# circuit1.net
KiCad netlist of a schematic drawn in EAGLE
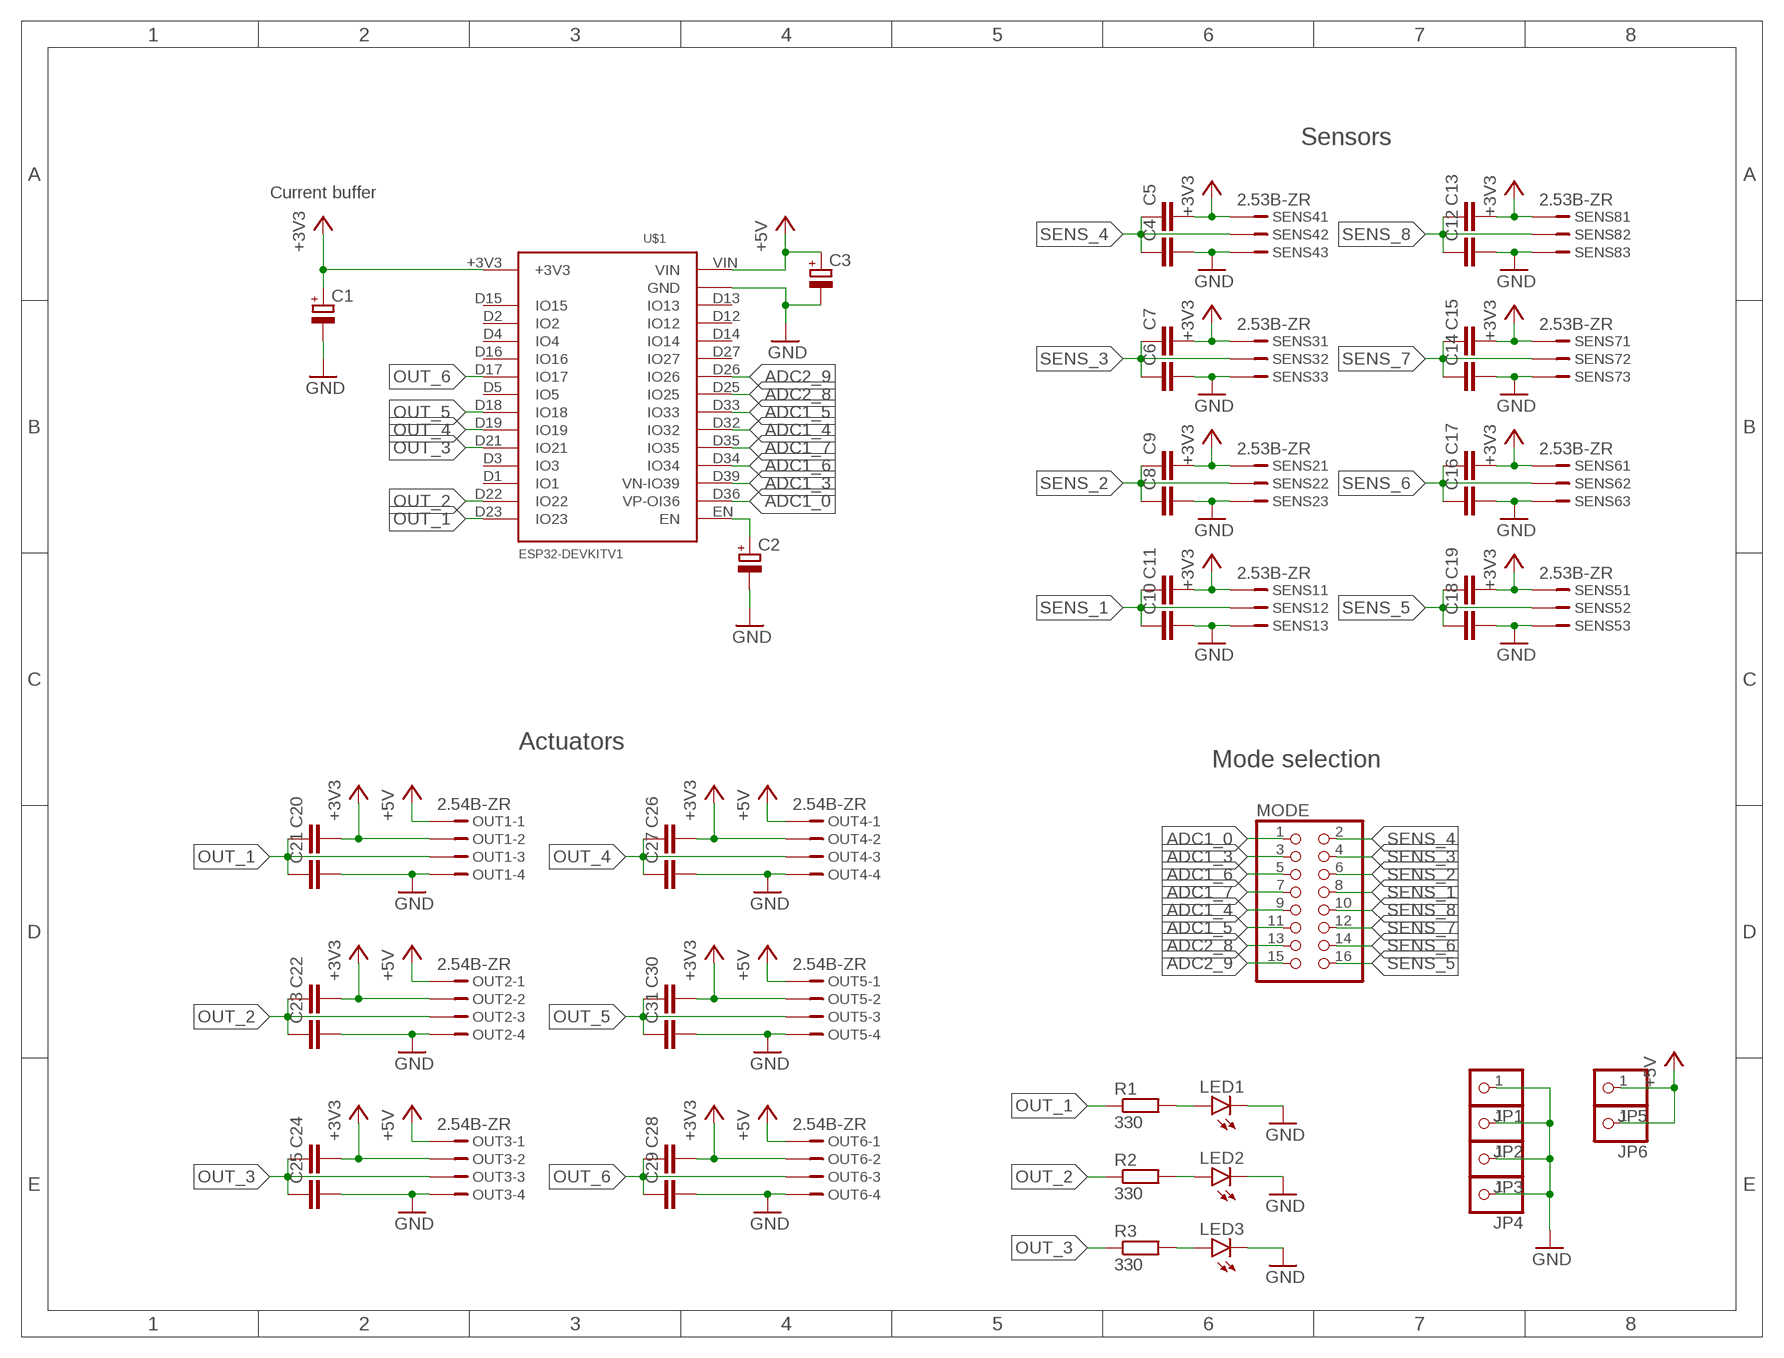
[diagram p0: schematic, sheet 1]

(export (version "E")
  (design (tool "Eeschema 10.0.6"))
  (components
    (comp (ref "C1")
      (value "CPOL-EUE3.5-8")
      (footprint "eagle-import:E3,5-8")
      (libsource (lib "eagle-import") (part "CPOL-EUE3.5-8"))
    )
    (comp (ref "C2")
      (value "CPOL-EUE3.5-8")
      (footprint "eagle-import:E3,5-8")
      (libsource (lib "eagle-import") (part "CPOL-EUE3.5-8"))
    )
    (comp (ref "C3")
      (value "CPOL-EUE3.5-8")
      (footprint "eagle-import:E3,5-8")
      (libsource (lib "eagle-import") (part "CPOL-EUE3.5-8"))
    )
    (comp (ref "C4")
      (value "C-EU025-030X050")
      (footprint "eagle-import:C025-030X050")
      (libsource (lib "eagle-import") (part "C-EU025-030X050"))
    )
    (comp (ref "C5")
      (value "C-EU025-030X050")
      (footprint "eagle-import:C025-030X050")
      (libsource (lib "eagle-import") (part "C-EU025-030X050"))
    )
    (comp (ref "C6")
      (value "C-EU025-030X050")
      (footprint "eagle-import:C025-030X050")
      (libsource (lib "eagle-import") (part "C-EU025-030X050"))
    )
    (comp (ref "C7")
      (value "C-EU025-030X050")
      (footprint "eagle-import:C025-030X050")
      (libsource (lib "eagle-import") (part "C-EU025-030X050"))
    )
    (comp (ref "C8")
      (value "C-EU025-030X050")
      (footprint "eagle-import:C025-030X050")
      (libsource (lib "eagle-import") (part "C-EU025-030X050"))
    )
    (comp (ref "C9")
      (value "C-EU025-030X050")
      (footprint "eagle-import:C025-030X050")
      (libsource (lib "eagle-import") (part "C-EU025-030X050"))
    )
    (comp (ref "C10")
      (value "C-EU025-030X050")
      (footprint "eagle-import:C025-030X050")
      (libsource (lib "eagle-import") (part "C-EU025-030X050"))
    )
    (comp (ref "C11")
      (value "C-EU025-030X050")
      (footprint "eagle-import:C025-030X050")
      (libsource (lib "eagle-import") (part "C-EU025-030X050"))
    )
    (comp (ref "C12")
      (value "C-EU025-030X050")
      (footprint "eagle-import:C025-030X050")
      (libsource (lib "eagle-import") (part "C-EU025-030X050"))
    )
    (comp (ref "C13")
      (value "C-EU025-030X050")
      (footprint "eagle-import:C025-030X050")
      (libsource (lib "eagle-import") (part "C-EU025-030X050"))
    )
    (comp (ref "C14")
      (value "C-EU025-030X050")
      (footprint "eagle-import:C025-030X050")
      (libsource (lib "eagle-import") (part "C-EU025-030X050"))
    )
    (comp (ref "C15")
      (value "C-EU025-030X050")
      (footprint "eagle-import:C025-030X050")
      (libsource (lib "eagle-import") (part "C-EU025-030X050"))
    )
    (comp (ref "C16")
      (value "C-EU025-030X050")
      (footprint "eagle-import:C025-030X050")
      (libsource (lib "eagle-import") (part "C-EU025-030X050"))
    )
    (comp (ref "C17")
      (value "C-EU025-030X050")
      (footprint "eagle-import:C025-030X050")
      (libsource (lib "eagle-import") (part "C-EU025-030X050"))
    )
    (comp (ref "C18")
      (value "C-EU025-030X050")
      (footprint "eagle-import:C025-030X050")
      (libsource (lib "eagle-import") (part "C-EU025-030X050"))
    )
    (comp (ref "C19")
      (value "C-EU025-030X050")
      (footprint "eagle-import:C025-030X050")
      (libsource (lib "eagle-import") (part "C-EU025-030X050"))
    )
    (comp (ref "C20")
      (value "C-EU025-030X050")
      (footprint "eagle-import:C025-030X050")
      (libsource (lib "eagle-import") (part "C-EU025-030X050"))
    )
    (comp (ref "C21")
      (value "C-EU025-030X050")
      (footprint "eagle-import:C025-030X050")
      (libsource (lib "eagle-import") (part "C-EU025-030X050"))
    )
    (comp (ref "C22")
      (value "C-EU025-030X050")
      (footprint "eagle-import:C025-030X050")
      (libsource (lib "eagle-import") (part "C-EU025-030X050"))
    )
    (comp (ref "C23")
      (value "C-EU025-030X050")
      (footprint "eagle-import:C025-030X050")
      (libsource (lib "eagle-import") (part "C-EU025-030X050"))
    )
    (comp (ref "C24")
      (value "C-EU025-030X050")
      (footprint "eagle-import:C025-030X050")
      (libsource (lib "eagle-import") (part "C-EU025-030X050"))
    )
    (comp (ref "C25")
      (value "C-EU025-030X050")
      (footprint "eagle-import:C025-030X050")
      (libsource (lib "eagle-import") (part "C-EU025-030X050"))
    )
    (comp (ref "C26")
      (value "C-EU025-030X050")
      (footprint "eagle-import:C025-030X050")
      (libsource (lib "eagle-import") (part "C-EU025-030X050"))
    )
    (comp (ref "C27")
      (value "C-EU025-030X050")
      (footprint "eagle-import:C025-030X050")
      (libsource (lib "eagle-import") (part "C-EU025-030X050"))
    )
    (comp (ref "C28")
      (value "C-EU025-030X050")
      (footprint "eagle-import:C025-030X050")
      (libsource (lib "eagle-import") (part "C-EU025-030X050"))
    )
    (comp (ref "C29")
      (value "C-EU025-030X050")
      (footprint "eagle-import:C025-030X050")
      (libsource (lib "eagle-import") (part "C-EU025-030X050"))
    )
    (comp (ref "C30")
      (value "C-EU025-030X050")
      (footprint "eagle-import:C025-030X050")
      (libsource (lib "eagle-import") (part "C-EU025-030X050"))
    )
    (comp (ref "C31")
      (value "C-EU025-030X050")
      (footprint "eagle-import:C025-030X050")
      (libsource (lib "eagle-import") (part "C-EU025-030X050"))
    )
    (comp (ref "JP1")
      (value "PINHD-1X1")
      (footprint "eagle-import:1X01")
      (libsource (lib "eagle-import") (part "PINHD-1X1"))
    )
    (comp (ref "JP2")
      (value "PINHD-1X1")
      (footprint "eagle-import:1X01")
      (libsource (lib "eagle-import") (part "PINHD-1X1"))
    )
    (comp (ref "JP3")
      (value "PINHD-1X1")
      (footprint "eagle-import:1X01")
      (libsource (lib "eagle-import") (part "PINHD-1X1"))
    )
    (comp (ref "JP4")
      (value "PINHD-1X1")
      (footprint "eagle-import:1X01")
      (libsource (lib "eagle-import") (part "PINHD-1X1"))
    )
    (comp (ref "JP5")
      (value "PINHD-1X1")
      (footprint "eagle-import:1X01")
      (libsource (lib "eagle-import") (part "PINHD-1X1"))
    )
    (comp (ref "JP6")
      (value "PINHD-1X1")
      (footprint "eagle-import:1X01")
      (libsource (lib "eagle-import") (part "PINHD-1X1"))
    )
    (comp (ref "LED1")
      (value "LED3MM")
      (footprint "eagle-import:LED3MM")
      (libsource (lib "eagle-import") (part "LED3MM"))
    )
    (comp (ref "LED2")
      (value "LED3MM")
      (footprint "eagle-import:LED3MM")
      (libsource (lib "eagle-import") (part "LED3MM"))
    )
    (comp (ref "LED3")
      (value "LED3MM")
      (footprint "eagle-import:LED3MM")
      (libsource (lib "eagle-import") (part "LED3MM"))
    )
    (comp (ref "MODE")
      (value "PINHD-2X8")
      (footprint "eagle-import:2X08")
      (libsource (lib "eagle-import") (part "PINHD-2X8"))
    )
    (comp (ref "OUT1")
      (value "2.54B-ZR")
      (footprint "eagle-import:B4B-ZR2.5")
      (libsource (lib "eagle-import") (part "?4B-ZR2.5"))
    )
    (comp (ref "OUT2")
      (value "2.54B-ZR")
      (footprint "eagle-import:B4B-ZR2.5")
      (libsource (lib "eagle-import") (part "?4B-ZR2.5"))
    )
    (comp (ref "OUT3")
      (value "2.54B-ZR")
      (footprint "eagle-import:B4B-ZR2.5")
      (libsource (lib "eagle-import") (part "?4B-ZR2.5"))
    )
    (comp (ref "OUT4")
      (value "2.54B-ZR")
      (footprint "eagle-import:B4B-ZR2.5")
      (libsource (lib "eagle-import") (part "?4B-ZR2.5"))
    )
    (comp (ref "OUT5")
      (value "2.54B-ZR")
      (footprint "eagle-import:B4B-ZR2.5")
      (libsource (lib "eagle-import") (part "?4B-ZR2.5"))
    )
    (comp (ref "OUT6")
      (value "2.54B-ZR")
      (footprint "eagle-import:B4B-ZR2.5")
      (libsource (lib "eagle-import") (part "?4B-ZR2.5"))
    )
    (comp (ref "R1")
      (value "330")
      (footprint "eagle-import:0204_7")
      (libsource (lib "eagle-import") (part "R-EU_0204/7"))
    )
    (comp (ref "R2")
      (value "330")
      (footprint "eagle-import:0204_7")
      (libsource (lib "eagle-import") (part "R-EU_0204/7"))
    )
    (comp (ref "R3")
      (value "330")
      (footprint "eagle-import:0204_7")
      (libsource (lib "eagle-import") (part "R-EU_0204/7"))
    )
    (comp (ref "SENS1")
      (value "2.53B-ZR")
      (footprint "eagle-import:B3B-ZR2.5")
      (libsource (lib "eagle-import") (part "?3B-ZR2.5"))
    )
    (comp (ref "SENS2")
      (value "2.53B-ZR")
      (footprint "eagle-import:B3B-ZR2.5")
      (libsource (lib "eagle-import") (part "?3B-ZR2.5"))
    )
    (comp (ref "SENS3")
      (value "2.53B-ZR")
      (footprint "eagle-import:B3B-ZR2.5")
      (libsource (lib "eagle-import") (part "?3B-ZR2.5"))
    )
    (comp (ref "SENS4")
      (value "2.53B-ZR")
      (footprint "eagle-import:B3B-ZR2.5")
      (libsource (lib "eagle-import") (part "?3B-ZR2.5"))
    )
    (comp (ref "SENS5")
      (value "2.53B-ZR")
      (footprint "eagle-import:B3B-ZR2.5")
      (libsource (lib "eagle-import") (part "?3B-ZR2.5"))
    )
    (comp (ref "SENS6")
      (value "2.53B-ZR")
      (footprint "eagle-import:B3B-ZR2.5")
      (libsource (lib "eagle-import") (part "?3B-ZR2.5"))
    )
    (comp (ref "SENS7")
      (value "2.53B-ZR")
      (footprint "eagle-import:B3B-ZR2.5")
      (libsource (lib "eagle-import") (part "?3B-ZR2.5"))
    )
    (comp (ref "SENS8")
      (value "2.53B-ZR")
      (footprint "eagle-import:B3B-ZR2.5")
      (libsource (lib "eagle-import") (part "?3B-ZR2.5"))
    )
    (comp (ref "U$1")
      (value "ESP32DEVKITV1")
      (footprint "eagle-import:ESP32-DEVKITV1")
      (libsource (lib "eagle-import") (part "ESP32DEVKITV1"))
    )
  )
  (nets
    (net (code "1") (name "+3V3") (class "Default")
      (node (ref "C1") (pin "+") (pinfunction "+_+") (pintype "passive"))
      (node (ref "C11") (pin "2") (pinfunction "2_2") (pintype "passive"))
      (node (ref "C13") (pin "2") (pinfunction "2_2") (pintype "passive"))
      (node (ref "C15") (pin "2") (pinfunction "2_2") (pintype "passive"))
      (node (ref "C17") (pin "2") (pinfunction "2_2") (pintype "passive"))
      (node (ref "C19") (pin "2") (pinfunction "2_2") (pintype "passive"))
      (node (ref "C20") (pin "2") (pinfunction "2_2") (pintype "passive"))
      (node (ref "C22") (pin "2") (pinfunction "2_2") (pintype "passive"))
      (node (ref "C24") (pin "2") (pinfunction "2_2") (pintype "passive"))
      (node (ref "C26") (pin "2") (pinfunction "2_2") (pintype "passive"))
      (node (ref "C28") (pin "2") (pinfunction "2_2") (pintype "passive"))
      (node (ref "C30") (pin "2") (pinfunction "2_2") (pintype "passive"))
      (node (ref "C5") (pin "2") (pinfunction "2_2") (pintype "passive"))
      (node (ref "C7") (pin "2") (pinfunction "2_2") (pintype "passive"))
      (node (ref "C9") (pin "2") (pinfunction "2_2") (pintype "passive"))
      (node (ref "OUT1") (pin "2") (pinfunction "1_2") (pintype "passive"))
      (node (ref "OUT2") (pin "2") (pinfunction "1_2") (pintype "passive"))
      (node (ref "OUT3") (pin "2") (pinfunction "1_2") (pintype "passive"))
      (node (ref "OUT4") (pin "2") (pinfunction "1_2") (pintype "passive"))
      (node (ref "OUT5") (pin "2") (pinfunction "1_2") (pintype "passive"))
      (node (ref "OUT6") (pin "2") (pinfunction "1_2") (pintype "passive"))
      (node (ref "SENS1") (pin "1") (pinfunction "1_1") (pintype "passive"))
      (node (ref "SENS2") (pin "1") (pinfunction "1_1") (pintype "passive"))
      (node (ref "SENS3") (pin "1") (pinfunction "1_1") (pintype "passive"))
      (node (ref "SENS4") (pin "1") (pinfunction "1_1") (pintype "passive"))
      (node (ref "SENS5") (pin "1") (pinfunction "1_1") (pintype "passive"))
      (node (ref "SENS6") (pin "1") (pinfunction "1_1") (pintype "passive"))
      (node (ref "SENS7") (pin "1") (pinfunction "1_1") (pintype "passive"))
      (node (ref "SENS8") (pin "1") (pinfunction "1_1") (pintype "passive"))
      (node (ref "U$1") (pin "+3V3") (pinfunction "+3V3_+3V3") (pintype "power_in"))
    )
    (net (code "2") (name "+5V") (class "Default")
      (node (ref "C3") (pin "+") (pinfunction "+_+") (pintype "passive"))
      (node (ref "JP5") (pin "1") (pinfunction "1_1") (pintype "passive"))
      (node (ref "JP6") (pin "1") (pinfunction "1_1") (pintype "passive"))
      (node (ref "OUT1") (pin "1") (pinfunction "1_1") (pintype "passive"))
      (node (ref "OUT2") (pin "1") (pinfunction "1_1") (pintype "passive"))
      (node (ref "OUT3") (pin "1") (pinfunction "1_1") (pintype "passive"))
      (node (ref "OUT4") (pin "1") (pinfunction "1_1") (pintype "passive"))
      (node (ref "OUT5") (pin "1") (pinfunction "1_1") (pintype "passive"))
      (node (ref "OUT6") (pin "1") (pinfunction "1_1") (pintype "passive"))
      (node (ref "U$1") (pin "VIN") (pinfunction "VIN_VIN") (pintype "power_in"))
    )
    (net (code "3") (name "ADC1_0") (class "Default")
      (node (ref "MODE") (pin "1") (pinfunction "1_1") (pintype "passive"))
      (node (ref "U$1") (pin "D36") (pinfunction "VP-OI36_D36") (pintype "bidirectional"))
    )
    (net (code "4") (name "ADC1_3") (class "Default")
      (node (ref "MODE") (pin "3") (pinfunction "3_3") (pintype "passive"))
      (node (ref "U$1") (pin "D39") (pinfunction "VN-IO39_D39") (pintype "bidirectional"))
    )
    (net (code "5") (name "ADC1_4") (class "Default")
      (node (ref "MODE") (pin "9") (pinfunction "9_9") (pintype "passive"))
      (node (ref "U$1") (pin "D32") (pinfunction "IO32_D32") (pintype "bidirectional"))
    )
    (net (code "6") (name "ADC1_5") (class "Default")
      (node (ref "MODE") (pin "11") (pinfunction "11_11") (pintype "passive"))
      (node (ref "U$1") (pin "D33") (pinfunction "IO33_D33") (pintype "bidirectional"))
    )
    (net (code "7") (name "ADC1_6") (class "Default")
      (node (ref "MODE") (pin "5") (pinfunction "5_5") (pintype "passive"))
      (node (ref "U$1") (pin "D34") (pinfunction "IO34_D34") (pintype "bidirectional"))
    )
    (net (code "8") (name "ADC1_7") (class "Default")
      (node (ref "MODE") (pin "7") (pinfunction "7_7") (pintype "passive"))
      (node (ref "U$1") (pin "D35") (pinfunction "IO35_D35") (pintype "bidirectional"))
    )
    (net (code "9") (name "ADC2_8") (class "Default")
      (node (ref "MODE") (pin "13") (pinfunction "13_13") (pintype "passive"))
      (node (ref "U$1") (pin "D25") (pinfunction "IO25_D25") (pintype "bidirectional"))
    )
    (net (code "10") (name "ADC2_9") (class "Default")
      (node (ref "MODE") (pin "15") (pinfunction "15_15") (pintype "passive"))
      (node (ref "U$1") (pin "D26") (pinfunction "IO26_D26") (pintype "bidirectional"))
    )
    (net (code "11") (name "GND") (class "Default")
      (node (ref "C1") (pin "-") (pinfunction "-_-") (pintype "passive"))
      (node (ref "C10") (pin "2") (pinfunction "2_2") (pintype "passive"))
      (node (ref "C12") (pin "2") (pinfunction "2_2") (pintype "passive"))
      (node (ref "C14") (pin "2") (pinfunction "2_2") (pintype "passive"))
      (node (ref "C16") (pin "2") (pinfunction "2_2") (pintype "passive"))
      (node (ref "C18") (pin "2") (pinfunction "2_2") (pintype "passive"))
      (node (ref "C2") (pin "-") (pinfunction "-_-") (pintype "passive"))
      (node (ref "C21") (pin "2") (pinfunction "2_2") (pintype "passive"))
      (node (ref "C23") (pin "2") (pinfunction "2_2") (pintype "passive"))
      (node (ref "C25") (pin "2") (pinfunction "2_2") (pintype "passive"))
      (node (ref "C27") (pin "2") (pinfunction "2_2") (pintype "passive"))
      (node (ref "C29") (pin "2") (pinfunction "2_2") (pintype "passive"))
      (node (ref "C3") (pin "-") (pinfunction "-_-") (pintype "passive"))
      (node (ref "C31") (pin "2") (pinfunction "2_2") (pintype "passive"))
      (node (ref "C4") (pin "2") (pinfunction "2_2") (pintype "passive"))
      (node (ref "C6") (pin "2") (pinfunction "2_2") (pintype "passive"))
      (node (ref "C8") (pin "2") (pinfunction "2_2") (pintype "passive"))
      (node (ref "JP1") (pin "1") (pinfunction "1_1") (pintype "passive"))
      (node (ref "JP2") (pin "1") (pinfunction "1_1") (pintype "passive"))
      (node (ref "JP3") (pin "1") (pinfunction "1_1") (pintype "passive"))
      (node (ref "JP4") (pin "1") (pinfunction "1_1") (pintype "passive"))
      (node (ref "LED1") (pin "K") (pinfunction "C_K") (pintype "passive"))
      (node (ref "LED2") (pin "K") (pinfunction "C_K") (pintype "passive"))
      (node (ref "LED3") (pin "K") (pinfunction "C_K") (pintype "passive"))
      (node (ref "OUT1") (pin "4") (pinfunction "1_4") (pintype "passive"))
      (node (ref "OUT2") (pin "4") (pinfunction "1_4") (pintype "passive"))
      (node (ref "OUT3") (pin "4") (pinfunction "1_4") (pintype "passive"))
      (node (ref "OUT4") (pin "4") (pinfunction "1_4") (pintype "passive"))
      (node (ref "OUT5") (pin "4") (pinfunction "1_4") (pintype "passive"))
      (node (ref "OUT6") (pin "4") (pinfunction "1_4") (pintype "passive"))
      (node (ref "SENS1") (pin "3") (pinfunction "1_3") (pintype "passive"))
      (node (ref "SENS2") (pin "3") (pinfunction "1_3") (pintype "passive"))
      (node (ref "SENS3") (pin "3") (pinfunction "1_3") (pintype "passive"))
      (node (ref "SENS4") (pin "3") (pinfunction "1_3") (pintype "passive"))
      (node (ref "SENS5") (pin "3") (pinfunction "1_3") (pintype "passive"))
      (node (ref "SENS6") (pin "3") (pinfunction "1_3") (pintype "passive"))
      (node (ref "SENS7") (pin "3") (pinfunction "1_3") (pintype "passive"))
      (node (ref "SENS8") (pin "3") (pinfunction "1_3") (pintype "passive"))
      (node (ref "U$1") (pin "GND") (pinfunction "GND_GND") (pintype "output"))
      (node (ref "U$1") (pin "GND@2") (pinfunction "GND_GND@2") (pintype "output"))
    )
    (net (code "12") (name "Net-(C2-Pad+)") (class "Default")
      (node (ref "C2") (pin "+") (pinfunction "+_+") (pintype "passive"))
      (node (ref "U$1") (pin "EN") (pinfunction "EN_EN") (pintype "bidirectional"))
    )
    (net (code "13") (name "Net-(LED1-PadA)") (class "Default")
      (node (ref "LED1") (pin "A") (pinfunction "A_A") (pintype "passive"))
      (node (ref "R1") (pin "2") (pinfunction "2_2") (pintype "passive"))
    )
    (net (code "14") (name "Net-(LED2-PadA)") (class "Default")
      (node (ref "LED2") (pin "A") (pinfunction "A_A") (pintype "passive"))
      (node (ref "R2") (pin "2") (pinfunction "2_2") (pintype "passive"))
    )
    (net (code "15") (name "Net-(LED3-PadA)") (class "Default")
      (node (ref "LED3") (pin "A") (pinfunction "A_A") (pintype "passive"))
      (node (ref "R3") (pin "2") (pinfunction "2_2") (pintype "passive"))
    )
    (net (code "16") (name "OUT_1") (class "Default")
      (node (ref "C20") (pin "1") (pinfunction "1_1") (pintype "passive"))
      (node (ref "C21") (pin "1") (pinfunction "1_1") (pintype "passive"))
      (node (ref "OUT1") (pin "3") (pinfunction "1_3") (pintype "passive"))
      (node (ref "R1") (pin "1") (pinfunction "1_1") (pintype "passive"))
      (node (ref "U$1") (pin "D23") (pinfunction "IO23_D23") (pintype "bidirectional"))
    )
    (net (code "17") (name "OUT_2") (class "Default")
      (node (ref "C22") (pin "1") (pinfunction "1_1") (pintype "passive"))
      (node (ref "C23") (pin "1") (pinfunction "1_1") (pintype "passive"))
      (node (ref "OUT2") (pin "3") (pinfunction "1_3") (pintype "passive"))
      (node (ref "R2") (pin "1") (pinfunction "1_1") (pintype "passive"))
      (node (ref "U$1") (pin "D22") (pinfunction "IO22_D22") (pintype "bidirectional"))
    )
    (net (code "18") (name "OUT_3") (class "Default")
      (node (ref "C24") (pin "1") (pinfunction "1_1") (pintype "passive"))
      (node (ref "C25") (pin "1") (pinfunction "1_1") (pintype "passive"))
      (node (ref "OUT3") (pin "3") (pinfunction "1_3") (pintype "passive"))
      (node (ref "R3") (pin "1") (pinfunction "1_1") (pintype "passive"))
      (node (ref "U$1") (pin "D21") (pinfunction "IO21_D21") (pintype "bidirectional"))
    )
    (net (code "19") (name "OUT_4") (class "Default")
      (node (ref "C26") (pin "1") (pinfunction "1_1") (pintype "passive"))
      (node (ref "C27") (pin "1") (pinfunction "1_1") (pintype "passive"))
      (node (ref "OUT4") (pin "3") (pinfunction "1_3") (pintype "passive"))
      (node (ref "U$1") (pin "D19") (pinfunction "IO19_D19") (pintype "bidirectional"))
    )
    (net (code "20") (name "OUT_5") (class "Default")
      (node (ref "C30") (pin "1") (pinfunction "1_1") (pintype "passive"))
      (node (ref "C31") (pin "1") (pinfunction "1_1") (pintype "passive"))
      (node (ref "OUT5") (pin "3") (pinfunction "1_3") (pintype "passive"))
      (node (ref "U$1") (pin "D18") (pinfunction "IO18_D18") (pintype "bidirectional"))
    )
    (net (code "21") (name "OUT_6") (class "Default")
      (node (ref "C28") (pin "1") (pinfunction "1_1") (pintype "passive"))
      (node (ref "C29") (pin "1") (pinfunction "1_1") (pintype "passive"))
      (node (ref "OUT6") (pin "3") (pinfunction "1_3") (pintype "passive"))
      (node (ref "U$1") (pin "D17") (pinfunction "IO17_D17") (pintype "bidirectional"))
    )
    (net (code "22") (name "SENS_1") (class "Default")
      (node (ref "C10") (pin "1") (pinfunction "1_1") (pintype "passive"))
      (node (ref "C11") (pin "1") (pinfunction "1_1") (pintype "passive"))
      (node (ref "MODE") (pin "8") (pinfunction "8_8") (pintype "passive"))
      (node (ref "SENS1") (pin "2") (pinfunction "1_2") (pintype "passive"))
    )
    (net (code "23") (name "SENS_2") (class "Default")
      (node (ref "C8") (pin "1") (pinfunction "1_1") (pintype "passive"))
      (node (ref "C9") (pin "1") (pinfunction "1_1") (pintype "passive"))
      (node (ref "MODE") (pin "6") (pinfunction "6_6") (pintype "passive"))
      (node (ref "SENS2") (pin "2") (pinfunction "1_2") (pintype "passive"))
    )
    (net (code "24") (name "SENS_3") (class "Default")
      (node (ref "C6") (pin "1") (pinfunction "1_1") (pintype "passive"))
      (node (ref "C7") (pin "1") (pinfunction "1_1") (pintype "passive"))
      (node (ref "MODE") (pin "4") (pinfunction "4_4") (pintype "passive"))
      (node (ref "SENS3") (pin "2") (pinfunction "1_2") (pintype "passive"))
    )
    (net (code "25") (name "SENS_4") (class "Default")
      (node (ref "C4") (pin "1") (pinfunction "1_1") (pintype "passive"))
      (node (ref "C5") (pin "1") (pinfunction "1_1") (pintype "passive"))
      (node (ref "MODE") (pin "2") (pinfunction "2_2") (pintype "passive"))
      (node (ref "SENS4") (pin "2") (pinfunction "1_2") (pintype "passive"))
    )
    (net (code "26") (name "SENS_5") (class "Default")
      (node (ref "C18") (pin "1") (pinfunction "1_1") (pintype "passive"))
      (node (ref "C19") (pin "1") (pinfunction "1_1") (pintype "passive"))
      (node (ref "MODE") (pin "16") (pinfunction "16_16") (pintype "passive"))
      (node (ref "SENS5") (pin "2") (pinfunction "1_2") (pintype "passive"))
    )
    (net (code "27") (name "SENS_6") (class "Default")
      (node (ref "C16") (pin "1") (pinfunction "1_1") (pintype "passive"))
      (node (ref "C17") (pin "1") (pinfunction "1_1") (pintype "passive"))
      (node (ref "MODE") (pin "14") (pinfunction "14_14") (pintype "passive"))
      (node (ref "SENS6") (pin "2") (pinfunction "1_2") (pintype "passive"))
    )
    (net (code "28") (name "SENS_7") (class "Default")
      (node (ref "C14") (pin "1") (pinfunction "1_1") (pintype "passive"))
      (node (ref "C15") (pin "1") (pinfunction "1_1") (pintype "passive"))
      (node (ref "MODE") (pin "12") (pinfunction "12_12") (pintype "passive"))
      (node (ref "SENS7") (pin "2") (pinfunction "1_2") (pintype "passive"))
    )
    (net (code "29") (name "SENS_8") (class "Default")
      (node (ref "C12") (pin "1") (pinfunction "1_1") (pintype "passive"))
      (node (ref "C13") (pin "1") (pinfunction "1_1") (pintype "passive"))
      (node (ref "MODE") (pin "10") (pinfunction "10_10") (pintype "passive"))
      (node (ref "SENS8") (pin "2") (pinfunction "1_2") (pintype "passive"))
    )
    (net (code "30") (name "unconnected-(U$1-IO1-PadD1)") (class "Default")
      (node (ref "U$1") (pin "D1") (pinfunction "IO1_D1") (pintype "bidirectional"))
    )
    (net (code "31") (name "unconnected-(U$1-IO2-PadD2)") (class "Default")
      (node (ref "U$1") (pin "D2") (pinfunction "IO2_D2") (pintype "bidirectional"))
    )
    (net (code "32") (name "unconnected-(U$1-IO3-PadD3)") (class "Default")
      (node (ref "U$1") (pin "D3") (pinfunction "IO3_D3") (pintype "bidirectional"))
    )
    (net (code "33") (name "unconnected-(U$1-IO4-PadD4)") (class "Default")
      (node (ref "U$1") (pin "D4") (pinfunction "IO4_D4") (pintype "bidirectional"))
    )
    (net (code "34") (name "unconnected-(U$1-IO5-PadD5)") (class "Default")
      (node (ref "U$1") (pin "D5") (pinfunction "IO5_D5") (pintype "bidirectional"))
    )
    (net (code "35") (name "unconnected-(U$1-IO12-PadD12)") (class "Default")
      (node (ref "U$1") (pin "D12") (pinfunction "IO12_D12") (pintype "bidirectional"))
    )
    (net (code "36") (name "unconnected-(U$1-IO13-PadD13)") (class "Default")
      (node (ref "U$1") (pin "D13") (pinfunction "IO13_D13") (pintype "bidirectional"))
    )
    (net (code "37") (name "unconnected-(U$1-IO14-PadD14)") (class "Default")
      (node (ref "U$1") (pin "D14") (pinfunction "IO14_D14") (pintype "bidirectional"))
    )
    (net (code "38") (name "unconnected-(U$1-IO15-PadD15)") (class "Default")
      (node (ref "U$1") (pin "D15") (pinfunction "IO15_D15") (pintype "bidirectional"))
    )
    (net (code "39") (name "unconnected-(U$1-IO16-PadD16)") (class "Default")
      (node (ref "U$1") (pin "D16") (pinfunction "IO16_D16") (pintype "bidirectional"))
    )
    (net (code "40") (name "unconnected-(U$1-IO27-PadD27)") (class "Default")
      (node (ref "U$1") (pin "D27") (pinfunction "IO27_D27") (pintype "bidirectional"))
    )
  )
)
